# homeboard1.net
KiCad netlist of a schematic drawn in EAGLE
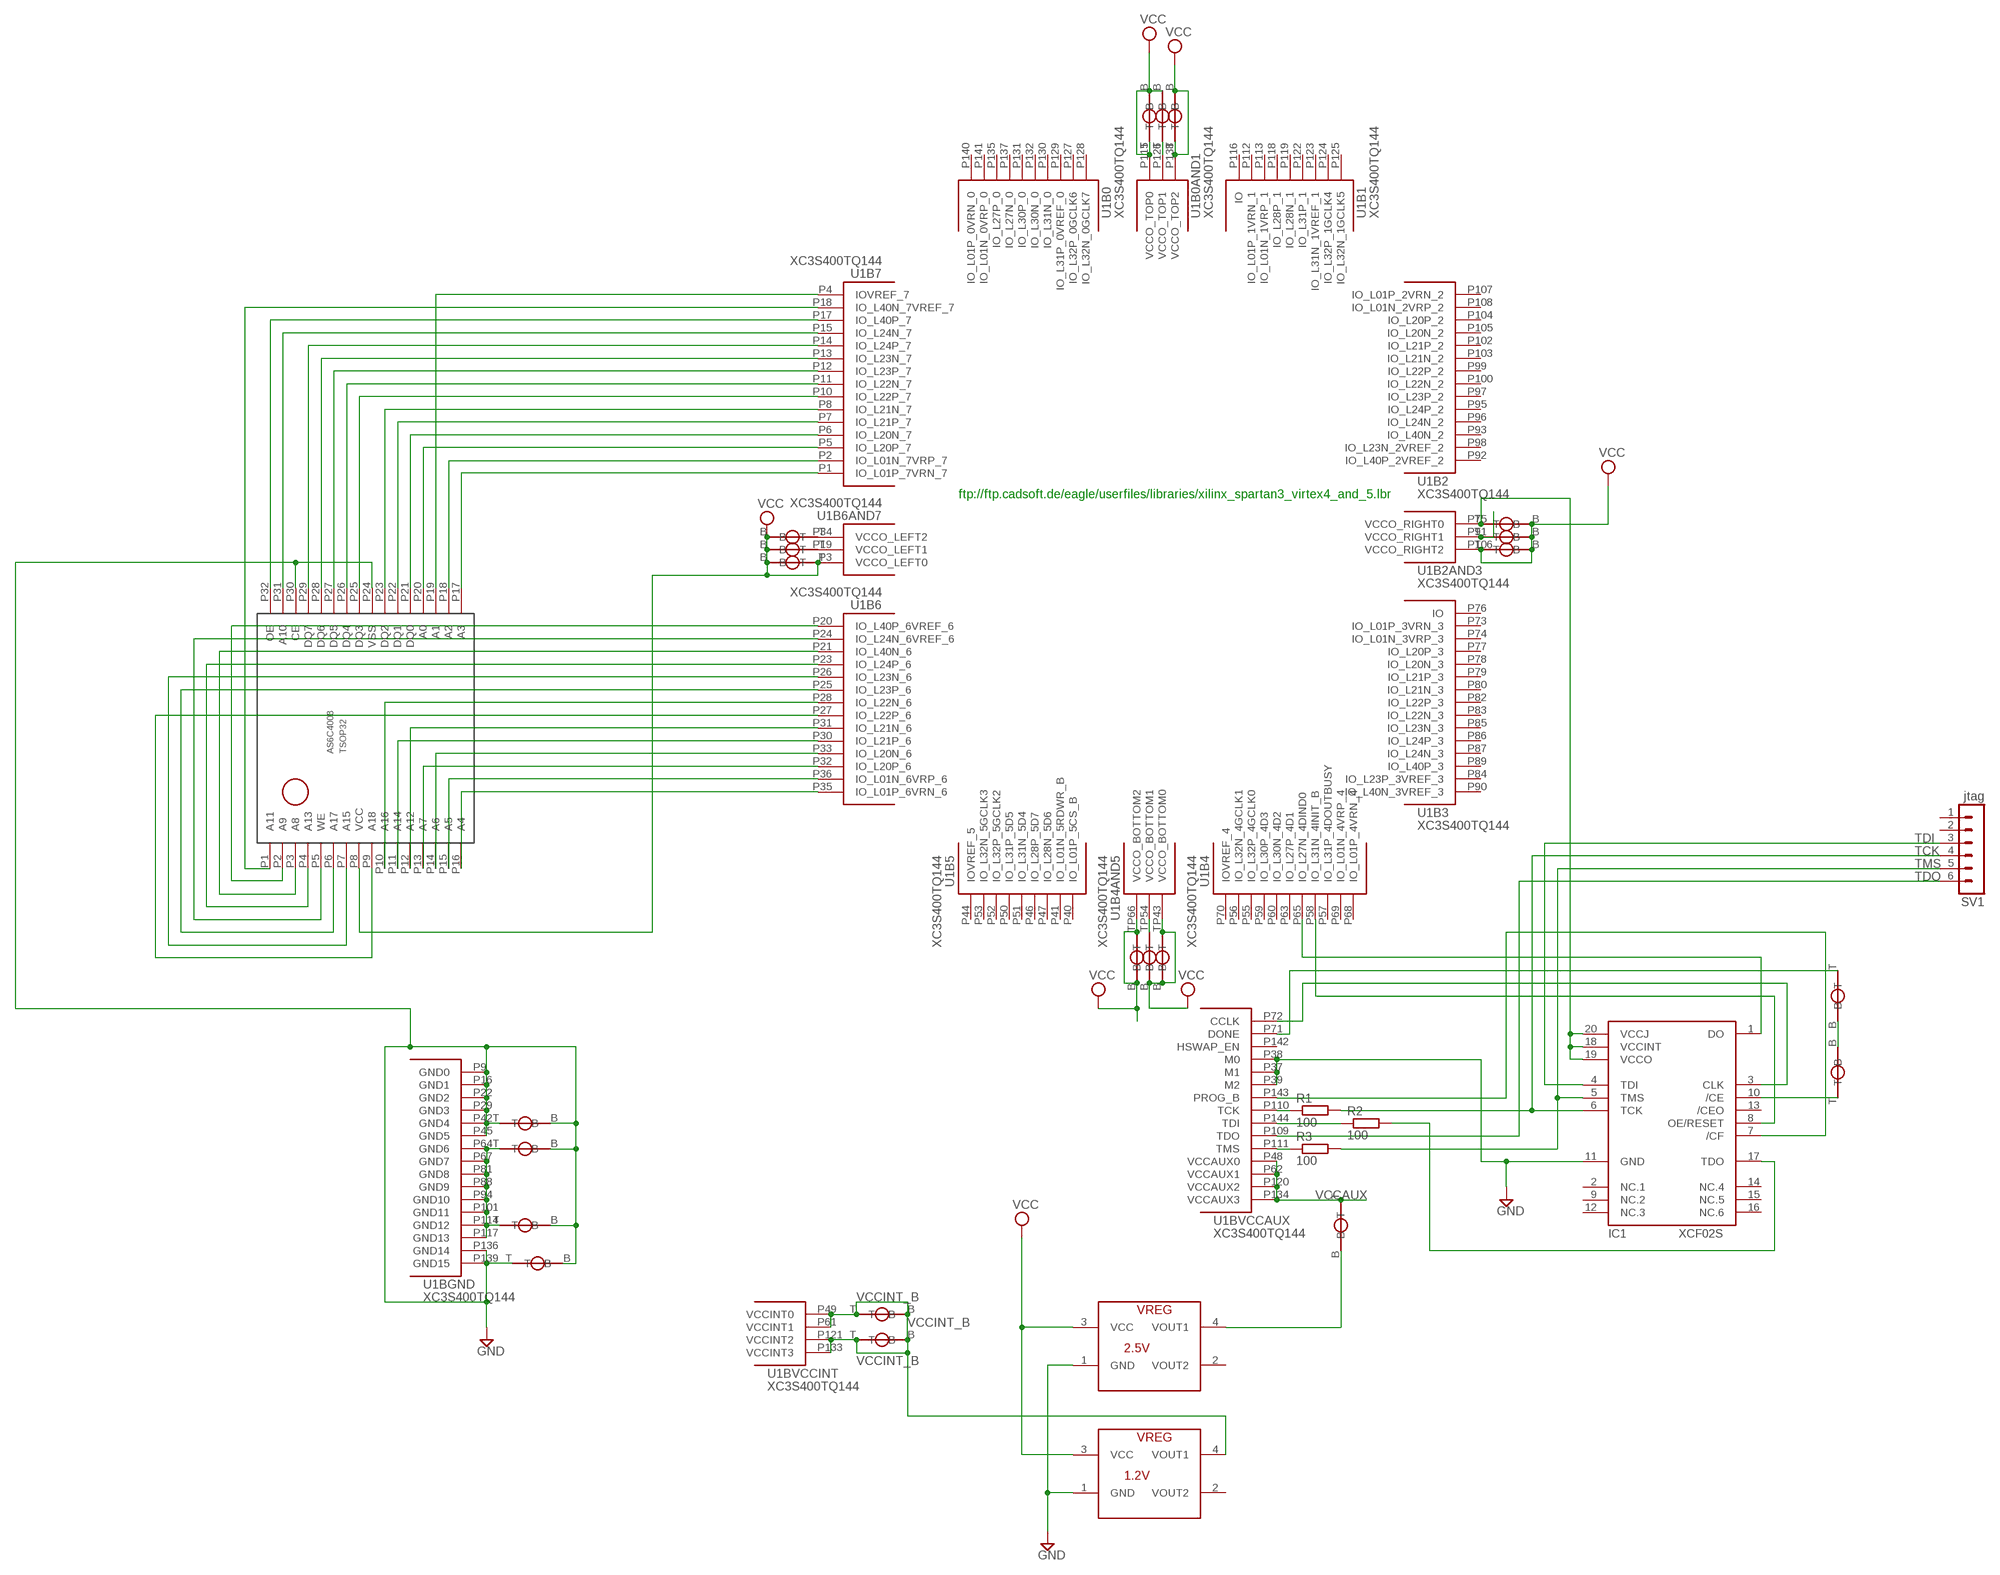
[diagram p0: schematic, sheet 1]

(export (version "E")
  (design (tool "Eeschema 10.0.6"))
  (components
    (comp (ref "IC1")
      (value "XCF02S")
      (footprint "eagle-import:VO20")
      (libsource (lib "eagle-import") (part "XCF02S"))
    )
    (comp (ref "R1")
      (value "100")
      (footprint "eagle-import:R0805")
      (libsource (lib "eagle-import") (part "R-EU_R0805"))
    )
    (comp (ref "R2")
      (value "100")
      (footprint "eagle-import:R0805")
      (libsource (lib "eagle-import") (part "R-EU_R0805"))
    )
    (comp (ref "R3")
      (value "100")
      (footprint "eagle-import:R0805")
      (libsource (lib "eagle-import") (part "R-EU_R0805"))
    )
    (comp (ref "SV1")
      (value "jtag")
      (footprint "eagle-import:MA06-1")
      (libsource (lib "eagle-import") (part "MA06-1"))
    )
    (comp (ref "U$1")
      (value "VIA_DIY")
      (footprint "eagle-import:VIA_DIY")
      (libsource (lib "eagle-import") (part "VIA_DIY"))
    )
    (comp (ref "U$2")
      (value "VIA_DIY")
      (footprint "eagle-import:VIA_DIY")
      (libsource (lib "eagle-import") (part "VIA_DIY"))
    )
    (comp (ref "U$3")
      (value "VIA_DIY")
      (footprint "eagle-import:VIA_DIY")
      (libsource (lib "eagle-import") (part "VIA_DIY"))
    )
    (comp (ref "U$4")
      (value "AS6C4008")
      (footprint "eagle-import:TSOP32")
      (libsource (lib "eagle-import") (part "AS6C4008"))
    )
    (comp (ref "U$5")
      (value "VIA_DIY")
      (footprint "eagle-import:VIA_DIY")
      (libsource (lib "eagle-import") (part "VIA_DIY"))
    )
    (comp (ref "U$6")
      (value "VIA_DIY")
      (footprint "eagle-import:VIA_DIY")
      (libsource (lib "eagle-import") (part "VIA_DIY"))
    )
    (comp (ref "U$7")
      (value "VIA_DIY")
      (footprint "eagle-import:VIA_DIY")
      (libsource (lib "eagle-import") (part "VIA_DIY"))
    )
    (comp (ref "U$8")
      (value "2.5V")
      (footprint "eagle-import:SOT223")
      (libsource (lib "eagle-import") (part "NX1117"))
    )
    (comp (ref "U$9")
      (value "1.2V")
      (footprint "eagle-import:SOT223")
      (libsource (lib "eagle-import") (part "NX1117"))
    )
    (comp (ref "U$10")
      (value "VIA_DIY")
      (footprint "eagle-import:VIA_DIY")
      (libsource (lib "eagle-import") (part "VIA_DIY"))
    )
    (comp (ref "U$11")
      (value "VIA_DIY")
      (footprint "eagle-import:VIA_DIY")
      (libsource (lib "eagle-import") (part "VIA_DIY"))
    )
    (comp (ref "U$12")
      (value "VIA_DIY")
      (footprint "eagle-import:VIA_DIY")
      (libsource (lib "eagle-import") (part "VIA_DIY"))
    )
    (comp (ref "U$13")
      (value "VIA_DIY")
      (footprint "eagle-import:VIA_DIY")
      (libsource (lib "eagle-import") (part "VIA_DIY"))
    )
    (comp (ref "U$14")
      (value "VIA_DIY")
      (footprint "eagle-import:VIA_DIY")
      (libsource (lib "eagle-import") (part "VIA_DIY"))
    )
    (comp (ref "U$15")
      (value "VIA_DIY")
      (footprint "eagle-import:VIA_DIY")
      (libsource (lib "eagle-import") (part "VIA_DIY"))
    )
    (comp (ref "U$18")
      (value "VIA_DIY")
      (footprint "eagle-import:VIA_DIY")
      (libsource (lib "eagle-import") (part "VIA_DIY"))
    )
    (comp (ref "U$19")
      (value "VIA_DIY")
      (footprint "eagle-import:VIA_DIY")
      (libsource (lib "eagle-import") (part "VIA_DIY"))
    )
    (comp (ref "U$20")
      (value "VIA_DIY")
      (footprint "eagle-import:VIA_DIY")
      (libsource (lib "eagle-import") (part "VIA_DIY"))
    )
    (comp (ref "U$23")
      (value "VIA_DIY")
      (footprint "eagle-import:VIA_DIY")
      (libsource (lib "eagle-import") (part "VIA_DIY"))
    )
    (comp (ref "U$25")
      (value "VIA_DIY")
      (footprint "eagle-import:VIA_DIY")
      (libsource (lib "eagle-import") (part "VIA_DIY"))
    )
    (comp (ref "U$26")
      (value "VIA_DIY")
      (footprint "eagle-import:VIA_DIY")
      (libsource (lib "eagle-import") (part "VIA_DIY"))
    )
    (comp (ref "U$27")
      (value "VIA_DIY")
      (footprint "eagle-import:VIA_DIY")
      (libsource (lib "eagle-import") (part "VIA_DIY"))
    )
    (comp (ref "U$28")
      (value "VIA_DIY")
      (footprint "eagle-import:VIA_DIY")
      (libsource (lib "eagle-import") (part "VIA_DIY"))
    )
    (comp (ref "U$29")
      (value "VIA_DIY")
      (footprint "eagle-import:VIA_DIY")
      (libsource (lib "eagle-import") (part "VIA_DIY"))
    )
    (comp (ref "U1")
      (value "XC3S400TQ144")
      (footprint "eagle-import:TQ144")
      (libsource (lib "eagle-import") (part "XC3S400TQ144"))
    )
  )
  (nets
    (net (code "1") (name "/TCK") (class "Default")
      (node (ref "IC1") (pin "6") (pinfunction "TCK_6") (pintype "bidirectional"))
      (node (ref "R1") (pin "2") (pinfunction "2_2") (pintype "passive"))
      (node (ref "SV1") (pin "4") (pinfunction "4_4") (pintype "passive"))
    )
    (net (code "2") (name "/TDI") (class "Default")
      (node (ref "IC1") (pin "4") (pinfunction "TDI_4") (pintype "bidirectional"))
      (node (ref "SV1") (pin "3") (pinfunction "3_3") (pintype "passive"))
    )
    (net (code "3") (name "/TDO") (class "Default")
      (node (ref "SV1") (pin "6") (pinfunction "6_6") (pintype "passive"))
      (node (ref "U1") (pin "P109") (pinfunction "TDO_P109") (pintype "bidirectional"))
    )
    (net (code "4") (name "/TMS") (class "Default")
      (node (ref "IC1") (pin "5") (pinfunction "TMS_5") (pintype "bidirectional"))
      (node (ref "R3") (pin "2") (pinfunction "2_2") (pintype "passive"))
      (node (ref "SV1") (pin "5") (pinfunction "5_5") (pintype "passive"))
    )
    (net (code "5") (name "/VCCAUX") (class "Default")
      (node (ref "U$11") (pin "T") (pinfunction "T_T") (pintype "bidirectional"))
      (node (ref "U1") (pin "P120") (pinfunction "VCCAUX2_P120") (pintype "passive"))
      (node (ref "U1") (pin "P134") (pinfunction "VCCAUX3_P134") (pintype "passive"))
      (node (ref "U1") (pin "P48") (pinfunction "VCCAUX0_P48") (pintype "passive"))
      (node (ref "U1") (pin "P62") (pinfunction "VCCAUX1_P62") (pintype "passive"))
    )
    (net (code "6") (name "/VCCINT_B") (class "Default")
      (node (ref "U$1") (pin "B") (pinfunction "B_B") (pintype "bidirectional"))
      (node (ref "U$1") (pin "T") (pinfunction "T_T") (pintype "bidirectional"))
      (node (ref "U$23") (pin "B") (pinfunction "B_B") (pintype "bidirectional"))
      (node (ref "U$23") (pin "T") (pinfunction "T_T") (pintype "bidirectional"))
      (node (ref "U$9") (pin "4") (pinfunction "VOUT1_4") (pintype "bidirectional"))
      (node (ref "U1") (pin "P121") (pinfunction "VCCINT2_P121") (pintype "passive"))
      (node (ref "U1") (pin "P133") (pinfunction "VCCINT3_P133") (pintype "passive"))
      (node (ref "U1") (pin "P49") (pinfunction "VCCINT0_P49") (pintype "passive"))
      (node (ref "U1") (pin "P61") (pinfunction "VCCINT1_P61") (pintype "passive"))
    )
    (net (code "7") (name "GND") (class "Default")
      (node (ref "IC1") (pin "11") (pinfunction "GND_11") (pintype "bidirectional"))
      (node (ref "U$2") (pin "B") (pinfunction "B_B") (pintype "bidirectional"))
      (node (ref "U$20") (pin "B") (pinfunction "B_B") (pintype "bidirectional"))
      (node (ref "U$3") (pin "B") (pinfunction "B_B") (pintype "bidirectional"))
      (node (ref "U$3") (pin "T") (pinfunction "T_T") (pintype "bidirectional"))
      (node (ref "U$4") (pin "P24") (pinfunction "VSS_P24") (pintype "bidirectional"))
      (node (ref "U$4") (pin "P30") (pinfunction "CE_P30") (pintype "bidirectional"))
      (node (ref "U$5") (pin "B") (pinfunction "B_B") (pintype "bidirectional"))
      (node (ref "U$5") (pin "T") (pinfunction "T_T") (pintype "bidirectional"))
      (node (ref "U$8") (pin "1") (pinfunction "GND_1") (pintype "bidirectional"))
      (node (ref "U$9") (pin "1") (pinfunction "GND_1") (pintype "bidirectional"))
      (node (ref "U1") (pin "P136") (pinfunction "GND14_P136") (pintype "passive"))
      (node (ref "U1") (pin "P139") (pinfunction "GND15_P139") (pintype "passive"))
      (node (ref "U1") (pin "P16") (pinfunction "GND1_P16") (pintype "passive"))
      (node (ref "U1") (pin "P22") (pinfunction "GND2_P22") (pintype "passive"))
      (node (ref "U1") (pin "P29") (pinfunction "GND3_P29") (pintype "passive"))
      (node (ref "U1") (pin "P37") (pinfunction "M1_P37") (pintype "bidirectional"))
      (node (ref "U1") (pin "P38") (pinfunction "M0_P38") (pintype "bidirectional"))
      (node (ref "U1") (pin "P39") (pinfunction "M2_P39") (pintype "bidirectional"))
      (node (ref "U1") (pin "P42") (pinfunction "GND4_P42") (pintype "passive"))
      (node (ref "U1") (pin "P45") (pinfunction "GND5_P45") (pintype "passive"))
      (node (ref "U1") (pin "P9") (pinfunction "GND0_P9") (pintype "passive"))
    )
    (net (code "8") (name "Net-(IC1-CLK)") (class "Default")
      (node (ref "IC1") (pin "3") (pinfunction "CLK_3") (pintype "bidirectional"))
      (node (ref "U1") (pin "P72") (pinfunction "CCLK_P72") (pintype "bidirectional"))
    )
    (net (code "9") (name "Net-(IC1-DO)") (class "Default")
      (node (ref "IC1") (pin "1") (pinfunction "DO_1") (pintype "bidirectional"))
      (node (ref "U1") (pin "P65") (pinfunction "IO_L27N_4DIND0_P65") (pintype "bidirectional"))
    )
    (net (code "10") (name "Net-(IC1-OE{slash}RESET)") (class "Default")
      (node (ref "IC1") (pin "8") (pinfunction "OE/RESET_8") (pintype "bidirectional"))
      (node (ref "U1") (pin "P58") (pinfunction "IO_L31N_4INIT_B_P58") (pintype "bidirectional"))
    )
    (net (code "11") (name "Net-(IC1-TDO)") (class "Default")
      (node (ref "IC1") (pin "17") (pinfunction "TDO_17") (pintype "bidirectional"))
      (node (ref "R2") (pin "2") (pinfunction "2_2") (pintype "passive"))
    )
    (net (code "12") (name "Net-(IC1-VCCINT)") (class "Default")
      (node (ref "IC1") (pin "18") (pinfunction "VCCINT_18") (pintype "bidirectional"))
      (node (ref "IC1") (pin "19") (pinfunction "VCCO_19") (pintype "bidirectional"))
      (node (ref "IC1") (pin "20") (pinfunction "VCCJ_20") (pintype "bidirectional"))
      (node (ref "U$29") (pin "T") (pinfunction "T_T") (pintype "bidirectional"))
      (node (ref "U1") (pin "P75") (pinfunction "VCCO_RIGHT0_P75") (pintype "passive"))
    )
    (net (code "13") (name "Net-(IC1-{slash}CE)") (class "Default")
      (node (ref "IC1") (pin "10") (pinfunction "/CE_10") (pintype "bidirectional"))
      (node (ref "U$12") (pin "T") (pinfunction "T_T") (pintype "bidirectional"))
    )
    (net (code "14") (name "Net-(IC1-{slash}CF)") (class "Default")
      (node (ref "IC1") (pin "7") (pinfunction "/CF_7") (pintype "bidirectional"))
      (node (ref "U1") (pin "P143") (pinfunction "PROG_B_P143") (pintype "bidirectional"))
    )
    (net (code "15") (name "Net-(U$4-A0)") (class "Default")
      (node (ref "U$4") (pin "P20") (pinfunction "A0_P20") (pintype "bidirectional"))
      (node (ref "U1") (pin "P5") (pinfunction "IO_L20P_7_P5") (pintype "bidirectional"))
    )
    (net (code "16") (name "Net-(U$4-A1)") (class "Default")
      (node (ref "U$4") (pin "P19") (pinfunction "A1_P19") (pintype "bidirectional"))
      (node (ref "U1") (pin "P4") (pinfunction "IOVREF_7_P4") (pintype "bidirectional"))
    )
    (net (code "17") (name "Net-(U$4-A2)") (class "Default")
      (node (ref "U$4") (pin "P18") (pinfunction "A2_P18") (pintype "bidirectional"))
      (node (ref "U1") (pin "P2") (pinfunction "IO_L01N_7VRP_7_P2") (pintype "bidirectional"))
    )
    (net (code "18") (name "Net-(U$4-A3)") (class "Default")
      (node (ref "U$4") (pin "P17") (pinfunction "A3_P17") (pintype "bidirectional"))
      (node (ref "U1") (pin "P1") (pinfunction "IO_L01P_7VRN_7_P1") (pintype "bidirectional"))
    )
    (net (code "19") (name "Net-(U$4-A4)") (class "Default")
      (node (ref "U$4") (pin "P16") (pinfunction "A4_P16") (pintype "bidirectional"))
      (node (ref "U1") (pin "P35") (pinfunction "IO_L01P_6VRN_6_P35") (pintype "bidirectional"))
    )
    (net (code "20") (name "Net-(U$4-A5)") (class "Default")
      (node (ref "U$4") (pin "P15") (pinfunction "A5_P15") (pintype "bidirectional"))
      (node (ref "U1") (pin "P36") (pinfunction "IO_L01N_6VRP_6_P36") (pintype "bidirectional"))
    )
    (net (code "21") (name "Net-(U$4-A6)") (class "Default")
      (node (ref "U$4") (pin "P14") (pinfunction "A6_P14") (pintype "bidirectional"))
      (node (ref "U1") (pin "P33") (pinfunction "IO_L20N_6_P33") (pintype "bidirectional"))
    )
    (net (code "22") (name "Net-(U$4-A7)") (class "Default")
      (node (ref "U$4") (pin "P13") (pinfunction "A7_P13") (pintype "bidirectional"))
      (node (ref "U1") (pin "P32") (pinfunction "IO_L20P_6_P32") (pintype "bidirectional"))
    )
    (net (code "23") (name "Net-(U$4-A8)") (class "Default")
      (node (ref "U$4") (pin "P3") (pinfunction "A8_P3") (pintype "bidirectional"))
      (node (ref "U1") (pin "P21") (pinfunction "IO_L40N_6_P21") (pintype "bidirectional"))
    )
    (net (code "24") (name "Net-(U$4-A9)") (class "Default")
      (node (ref "U$4") (pin "P2") (pinfunction "A9_P2") (pintype "bidirectional"))
      (node (ref "U1") (pin "P20") (pinfunction "IO_L40P_6VREF_6_P20") (pintype "bidirectional"))
    )
    (net (code "25") (name "Net-(U$4-A10)") (class "Default")
      (node (ref "U$4") (pin "P31") (pinfunction "A10_P31") (pintype "bidirectional"))
      (node (ref "U1") (pin "P15") (pinfunction "IO_L24N_7_P15") (pintype "bidirectional"))
    )
    (net (code "26") (name "Net-(U$4-A11)") (class "Default")
      (node (ref "U$4") (pin "P1") (pinfunction "A11_P1") (pintype "bidirectional"))
      (node (ref "U1") (pin "P18") (pinfunction "IO_L40N_7VREF_7_P18") (pintype "bidirectional"))
    )
    (net (code "27") (name "Net-(U$4-A12)") (class "Default")
      (node (ref "U$4") (pin "P12") (pinfunction "A12_P12") (pintype "bidirectional"))
      (node (ref "U1") (pin "P31") (pinfunction "IO_L21N_6_P31") (pintype "bidirectional"))
    )
    (net (code "28") (name "Net-(U$4-A13)") (class "Default")
      (node (ref "U$4") (pin "P4") (pinfunction "A13_P4") (pintype "bidirectional"))
      (node (ref "U1") (pin "P23") (pinfunction "IO_L24P_6_P23") (pintype "bidirectional"))
    )
    (net (code "29") (name "Net-(U$4-A14)") (class "Default")
      (node (ref "U$4") (pin "P11") (pinfunction "A14_P11") (pintype "bidirectional"))
      (node (ref "U1") (pin "P30") (pinfunction "IO_L21P_6_P30") (pintype "bidirectional"))
    )
    (net (code "30") (name "Net-(U$4-A15)") (class "Default")
      (node (ref "U$4") (pin "P7") (pinfunction "A15_P7") (pintype "bidirectional"))
      (node (ref "U1") (pin "P26") (pinfunction "IO_L23N_6_P26") (pintype "bidirectional"))
    )
    (net (code "31") (name "Net-(U$4-A16)") (class "Default")
      (node (ref "U$4") (pin "P10") (pinfunction "A16_P10") (pintype "bidirectional"))
      (node (ref "U1") (pin "P28") (pinfunction "IO_L22N_6_P28") (pintype "bidirectional"))
    )
    (net (code "32") (name "Net-(U$4-A17)") (class "Default")
      (node (ref "U$4") (pin "P6") (pinfunction "A17_P6") (pintype "bidirectional"))
      (node (ref "U1") (pin "P25") (pinfunction "IO_L23P_6_P25") (pintype "bidirectional"))
    )
    (net (code "33") (name "Net-(U$4-A18)") (class "Default")
      (node (ref "U$4") (pin "P9") (pinfunction "A18_P9") (pintype "bidirectional"))
      (node (ref "U1") (pin "P27") (pinfunction "IO_L22P_6_P27") (pintype "bidirectional"))
    )
    (net (code "34") (name "Net-(U$4-DQ0)") (class "Default")
      (node (ref "U$4") (pin "P21") (pinfunction "DQ0_P21") (pintype "bidirectional"))
      (node (ref "U1") (pin "P6") (pinfunction "IO_L20N_7_P6") (pintype "bidirectional"))
    )
    (net (code "35") (name "Net-(U$4-DQ1)") (class "Default")
      (node (ref "U$4") (pin "P22") (pinfunction "DQ1_P22") (pintype "bidirectional"))
      (node (ref "U1") (pin "P7") (pinfunction "IO_L21P_7_P7") (pintype "bidirectional"))
    )
    (net (code "36") (name "Net-(U$4-DQ2)") (class "Default")
      (node (ref "U$4") (pin "P23") (pinfunction "DQ2_P23") (pintype "bidirectional"))
      (node (ref "U1") (pin "P8") (pinfunction "IO_L21N_7_P8") (pintype "bidirectional"))
    )
    (net (code "37") (name "Net-(U$4-DQ3)") (class "Default")
      (node (ref "U$4") (pin "P25") (pinfunction "DQ3_P25") (pintype "bidirectional"))
      (node (ref "U1") (pin "P10") (pinfunction "IO_L22P_7_P10") (pintype "bidirectional"))
    )
    (net (code "38") (name "Net-(U$4-DQ4)") (class "Default")
      (node (ref "U$4") (pin "P26") (pinfunction "DQ4_P26") (pintype "bidirectional"))
      (node (ref "U1") (pin "P11") (pinfunction "IO_L22N_7_P11") (pintype "bidirectional"))
    )
    (net (code "39") (name "Net-(U$4-DQ5)") (class "Default")
      (node (ref "U$4") (pin "P27") (pinfunction "DQ5_P27") (pintype "bidirectional"))
      (node (ref "U1") (pin "P12") (pinfunction "IO_L23P_7_P12") (pintype "bidirectional"))
    )
    (net (code "40") (name "Net-(U$4-DQ6)") (class "Default")
      (node (ref "U$4") (pin "P28") (pinfunction "DQ6_P28") (pintype "bidirectional"))
      (node (ref "U1") (pin "P13") (pinfunction "IO_L23N_7_P13") (pintype "bidirectional"))
    )
    (net (code "41") (name "Net-(U$4-DQ7)") (class "Default")
      (node (ref "U$4") (pin "P29") (pinfunction "DQ7_P29") (pintype "bidirectional"))
      (node (ref "U1") (pin "P14") (pinfunction "IO_L24P_7_P14") (pintype "bidirectional"))
    )
    (net (code "42") (name "Net-(U$4-OE)") (class "Default")
      (node (ref "U$4") (pin "P32") (pinfunction "OE_P32") (pintype "bidirectional"))
      (node (ref "U1") (pin "P17") (pinfunction "IO_L40P_7_P17") (pintype "bidirectional"))
    )
    (net (code "43") (name "Net-(U$4-WE)") (class "Default")
      (node (ref "U$4") (pin "P5") (pinfunction "WE_P5") (pintype "bidirectional"))
      (node (ref "U1") (pin "P24") (pinfunction "IO_L24N_6VREF_6_P24") (pintype "bidirectional"))
    )
    (net (code "44") (name "Net-(U$8-VOUT1)") (class "Default")
      (node (ref "U$11") (pin "B") (pinfunction "B_B") (pintype "bidirectional"))
      (node (ref "U$8") (pin "4") (pinfunction "VOUT1_4") (pintype "bidirectional"))
    )
    (net (code "45") (name "Net-(U$12-PadB)") (class "Default")
      (node (ref "U$12") (pin "B") (pinfunction "B_B") (pintype "bidirectional"))
      (node (ref "U$13") (pin "B") (pinfunction "B_B") (pintype "bidirectional"))
    )
    (net (code "46") (name "Net-(U1B-VCCO_TOP1)") (class "Default")
      (node (ref "U$10") (pin "T") (pinfunction "T_T") (pintype "bidirectional"))
      (node (ref "U1") (pin "P126") (pinfunction "VCCO_TOP1_P126") (pintype "passive"))
    )
    (net (code "47") (name "Net-(U1E-VCCO_RIGHT1)") (class "Default")
      (node (ref "U$28") (pin "T") (pinfunction "T_T") (pintype "bidirectional"))
      (node (ref "U1") (pin "P91") (pinfunction "VCCO_RIGHT1_P91") (pintype "passive"))
    )
    (net (code "48") (name "Net-(U1H-VCCO_BOTTOM1)") (class "Default")
      (node (ref "U$25") (pin "T") (pinfunction "T_T") (pintype "bidirectional"))
      (node (ref "U1") (pin "P54") (pinfunction "VCCO_BOTTOM1_P54") (pintype "passive"))
    )
    (net (code "49") (name "Net-(U1K-VCCO_LEFT1)") (class "Default")
      (node (ref "U$15") (pin "T") (pinfunction "T_T") (pintype "bidirectional"))
      (node (ref "U1") (pin "P19") (pinfunction "VCCO_LEFT1_P19") (pintype "passive"))
    )
    (net (code "50") (name "Net-(U1K-VCCO_LEFT2)") (class "Default")
      (node (ref "U$14") (pin "T") (pinfunction "T_T") (pintype "bidirectional"))
      (node (ref "U1") (pin "P34") (pinfunction "VCCO_LEFT2_P34") (pintype "passive"))
    )
    (net (code "51") (name "Net-(U1M-GND10)") (class "Default")
      (node (ref "U$2") (pin "T") (pinfunction "T_T") (pintype "bidirectional"))
      (node (ref "U$20") (pin "T") (pinfunction "T_T") (pintype "bidirectional"))
      (node (ref "U1") (pin "P101") (pinfunction "GND11_P101") (pintype "passive"))
      (node (ref "U1") (pin "P114") (pinfunction "GND12_P114") (pintype "passive"))
      (node (ref "U1") (pin "P117") (pinfunction "GND13_P117") (pintype "passive"))
      (node (ref "U1") (pin "P64") (pinfunction "GND6_P64") (pintype "passive"))
      (node (ref "U1") (pin "P67") (pinfunction "GND7_P67") (pintype "passive"))
      (node (ref "U1") (pin "P81") (pinfunction "GND8_P81") (pintype "passive"))
      (node (ref "U1") (pin "P88") (pinfunction "GND9_P88") (pintype "passive"))
      (node (ref "U1") (pin "P94") (pinfunction "GND10_P94") (pintype "passive"))
    )
    (net (code "52") (name "Net-(U1N-DONE)") (class "Default")
      (node (ref "U$13") (pin "T") (pinfunction "T_T") (pintype "bidirectional"))
      (node (ref "U1") (pin "P71") (pinfunction "DONE_P71") (pintype "bidirectional"))
    )
    (net (code "53") (name "Net-(U1N-TCK)") (class "Default")
      (node (ref "R1") (pin "1") (pinfunction "1_1") (pintype "passive"))
      (node (ref "U1") (pin "P110") (pinfunction "TCK_P110") (pintype "bidirectional"))
    )
    (net (code "54") (name "Net-(U1N-TDI)") (class "Default")
      (node (ref "R2") (pin "1") (pinfunction "1_1") (pintype "passive"))
      (node (ref "U1") (pin "P144") (pinfunction "TDI_P144") (pintype "bidirectional"))
    )
    (net (code "55") (name "Net-(U1N-TMS)") (class "Default")
      (node (ref "R3") (pin "1") (pinfunction "1_1") (pintype "passive"))
      (node (ref "U1") (pin "P111") (pinfunction "TMS_P111") (pintype "bidirectional"))
    )
    (net (code "56") (name "VCC") (class "Default")
      (node (ref "U$10") (pin "B") (pinfunction "B_B") (pintype "bidirectional"))
      (node (ref "U$14") (pin "B") (pinfunction "B_B") (pintype "bidirectional"))
      (node (ref "U$15") (pin "B") (pinfunction "B_B") (pintype "bidirectional"))
      (node (ref "U$18") (pin "B") (pinfunction "B_B") (pintype "bidirectional"))
      (node (ref "U$18") (pin "T") (pinfunction "T_T") (pintype "bidirectional"))
      (node (ref "U$19") (pin "B") (pinfunction "B_B") (pintype "bidirectional"))
      (node (ref "U$19") (pin "T") (pinfunction "T_T") (pintype "bidirectional"))
      (node (ref "U$25") (pin "B") (pinfunction "B_B") (pintype "bidirectional"))
      (node (ref "U$26") (pin "B") (pinfunction "B_B") (pintype "bidirectional"))
      (node (ref "U$26") (pin "T") (pinfunction "T_T") (pintype "bidirectional"))
      (node (ref "U$27") (pin "B") (pinfunction "B_B") (pintype "bidirectional"))
      (node (ref "U$27") (pin "T") (pinfunction "T_T") (pintype "bidirectional"))
      (node (ref "U$28") (pin "B") (pinfunction "B_B") (pintype "bidirectional"))
      (node (ref "U$29") (pin "B") (pinfunction "B_B") (pintype "bidirectional"))
      (node (ref "U$4") (pin "P8") (pinfunction "VCC_P8") (pintype "bidirectional"))
      (node (ref "U$6") (pin "B") (pinfunction "B_B") (pintype "bidirectional"))
      (node (ref "U$6") (pin "T") (pinfunction "T_T") (pintype "bidirectional"))
      (node (ref "U$7") (pin "B") (pinfunction "B_B") (pintype "bidirectional"))
      (node (ref "U$7") (pin "T") (pinfunction "T_T") (pintype "bidirectional"))
      (node (ref "U$8") (pin "3") (pinfunction "VCC_3") (pintype "bidirectional"))
      (node (ref "U$9") (pin "3") (pinfunction "VCC_3") (pintype "bidirectional"))
      (node (ref "U1") (pin "P106") (pinfunction "VCCO_RIGHT2_P106") (pintype "passive"))
      (node (ref "U1") (pin "P115") (pinfunction "VCCO_TOP0_P115") (pintype "passive"))
      (node (ref "U1") (pin "P138") (pinfunction "VCCO_TOP2_P138") (pintype "passive"))
      (node (ref "U1") (pin "P3") (pinfunction "VCCO_LEFT0_P3") (pintype "passive"))
      (node (ref "U1") (pin "P43") (pinfunction "VCCO_BOTTOM0_P43") (pintype "passive"))
      (node (ref "U1") (pin "P66") (pinfunction "VCCO_BOTTOM2_P66") (pintype "passive"))
    )
    (net (code "57") (name "unconnected-(IC1-NC.1-Pad2)") (class "Default")
      (node (ref "IC1") (pin "2") (pinfunction "NC.1_2") (pintype "bidirectional"))
    )
    (net (code "58") (name "unconnected-(IC1-NC.2-Pad9)") (class "Default")
      (node (ref "IC1") (pin "9") (pinfunction "NC.2_9") (pintype "bidirectional"))
    )
    (net (code "59") (name "unconnected-(IC1-NC.3-Pad12)") (class "Default")
      (node (ref "IC1") (pin "12") (pinfunction "NC.3_12") (pintype "bidirectional"))
    )
    (net (code "60") (name "unconnected-(IC1-NC.4-Pad14)") (class "Default")
      (node (ref "IC1") (pin "14") (pinfunction "NC.4_14") (pintype "bidirectional"))
    )
    (net (code "61") (name "unconnected-(IC1-NC.5-Pad15)") (class "Default")
      (node (ref "IC1") (pin "15") (pinfunction "NC.5_15") (pintype "bidirectional"))
    )
    (net (code "62") (name "unconnected-(IC1-NC.6-Pad16)") (class "Default")
      (node (ref "IC1") (pin "16") (pinfunction "NC.6_16") (pintype "bidirectional"))
    )
    (net (code "63") (name "unconnected-(IC1-{slash}CEO-Pad13)") (class "Default")
      (node (ref "IC1") (pin "13") (pinfunction "/CEO_13") (pintype "bidirectional"))
    )
    (net (code "64") (name "unconnected-(SV1-Pad1)") (class "Default")
      (node (ref "SV1") (pin "1") (pinfunction "1_1") (pintype "passive"))
    )
    (net (code "65") (name "unconnected-(SV1-Pad2)") (class "Default")
      (node (ref "SV1") (pin "2") (pinfunction "2_2") (pintype "passive"))
    )
    (net (code "66") (name "unconnected-(U$8-VOUT2-Pad2)") (class "Default")
      (node (ref "U$8") (pin "2") (pinfunction "VOUT2_2") (pintype "bidirectional"))
    )
    (net (code "67") (name "unconnected-(U$9-VOUT2-Pad2)") (class "Default")
      (node (ref "U$9") (pin "2") (pinfunction "VOUT2_2") (pintype "bidirectional"))
    )
    (net (code "68") (name "unconnected-(U1A-IO_L01N_0VRP_0-PadP141)") (class "Default")
      (node (ref "U1") (pin "P141") (pinfunction "IO_L01N_0VRP_0_P141") (pintype "bidirectional"))
    )
    (net (code "69") (name "unconnected-(U1A-IO_L01P_0VRN_0-PadP140)") (class "Default")
      (node (ref "U1") (pin "P140") (pinfunction "IO_L01P_0VRN_0_P140") (pintype "bidirectional"))
    )
    (net (code "70") (name "unconnected-(U1A-IO_L27N_0-PadP137)") (class "Default")
      (node (ref "U1") (pin "P137") (pinfunction "IO_L27N_0_P137") (pintype "bidirectional"))
    )
    (net (code "71") (name "unconnected-(U1A-IO_L27P_0-PadP135)") (class "Default")
      (node (ref "U1") (pin "P135") (pinfunction "IO_L27P_0_P135") (pintype "bidirectional"))
    )
    (net (code "72") (name "unconnected-(U1A-IO_L30N_0-PadP132)") (class "Default")
      (node (ref "U1") (pin "P132") (pinfunction "IO_L30N_0_P132") (pintype "bidirectional"))
    )
    (net (code "73") (name "unconnected-(U1A-IO_L30P_0-PadP131)") (class "Default")
      (node (ref "U1") (pin "P131") (pinfunction "IO_L30P_0_P131") (pintype "bidirectional"))
    )
    (net (code "74") (name "unconnected-(U1A-IO_L31N_0-PadP130)") (class "Default")
      (node (ref "U1") (pin "P130") (pinfunction "IO_L31N_0_P130") (pintype "bidirectional"))
    )
    (net (code "75") (name "unconnected-(U1A-IO_L31P_0VREF_0-PadP129)") (class "Default")
      (node (ref "U1") (pin "P129") (pinfunction "IO_L31P_0VREF_0_P129") (pintype "bidirectional"))
    )
    (net (code "76") (name "unconnected-(U1A-IO_L32N_0GCLK7-PadP128)") (class "Default")
      (node (ref "U1") (pin "P128") (pinfunction "IO_L32N_0GCLK7_P128") (pintype "bidirectional"))
    )
    (net (code "77") (name "unconnected-(U1A-IO_L32P_0GCLK6-PadP127)") (class "Default")
      (node (ref "U1") (pin "P127") (pinfunction "IO_L32P_0GCLK6_P127") (pintype "bidirectional"))
    )
    (net (code "78") (name "unconnected-(U1C-IO-PadP116)") (class "Default")
      (node (ref "U1") (pin "P116") (pinfunction "IO_P116") (pintype "bidirectional"))
    )
    (net (code "79") (name "unconnected-(U1C-IO_L01N_1VRP_1-PadP113)") (class "Default")
      (node (ref "U1") (pin "P113") (pinfunction "IO_L01N_1VRP_1_P113") (pintype "bidirectional"))
    )
    (net (code "80") (name "unconnected-(U1C-IO_L01P_1VRN_1-PadP112)") (class "Default")
      (node (ref "U1") (pin "P112") (pinfunction "IO_L01P_1VRN_1_P112") (pintype "bidirectional"))
    )
    (net (code "81") (name "unconnected-(U1C-IO_L28N_1-PadP119)") (class "Default")
      (node (ref "U1") (pin "P119") (pinfunction "IO_L28N_1_P119") (pintype "bidirectional"))
    )
    (net (code "82") (name "unconnected-(U1C-IO_L28P_1-PadP118)") (class "Default")
      (node (ref "U1") (pin "P118") (pinfunction "IO_L28P_1_P118") (pintype "bidirectional"))
    )
    (net (code "83") (name "unconnected-(U1C-IO_L31N_1VREF_1-PadP123)") (class "Default")
      (node (ref "U1") (pin "P123") (pinfunction "IO_L31N_1VREF_1_P123") (pintype "bidirectional"))
    )
    (net (code "84") (name "unconnected-(U1C-IO_L31P_1-PadP122)") (class "Default")
      (node (ref "U1") (pin "P122") (pinfunction "IO_L31P_1_P122") (pintype "bidirectional"))
    )
    (net (code "85") (name "unconnected-(U1C-IO_L32N_1GCLK5-PadP125)") (class "Default")
      (node (ref "U1") (pin "P125") (pinfunction "IO_L32N_1GCLK5_P125") (pintype "bidirectional"))
    )
    (net (code "86") (name "unconnected-(U1C-IO_L32P_1GCLK4-PadP124)") (class "Default")
      (node (ref "U1") (pin "P124") (pinfunction "IO_L32P_1GCLK4_P124") (pintype "bidirectional"))
    )
    (net (code "87") (name "unconnected-(U1D-IO_L01N_2VRP_2-PadP108)") (class "Default")
      (node (ref "U1") (pin "P108") (pinfunction "IO_L01N_2VRP_2_P108") (pintype "bidirectional"))
    )
    (net (code "88") (name "unconnected-(U1D-IO_L01P_2VRN_2-PadP107)") (class "Default")
      (node (ref "U1") (pin "P107") (pinfunction "IO_L01P_2VRN_2_P107") (pintype "bidirectional"))
    )
    (net (code "89") (name "unconnected-(U1D-IO_L20N_2-PadP105)") (class "Default")
      (node (ref "U1") (pin "P105") (pinfunction "IO_L20N_2_P105") (pintype "bidirectional"))
    )
    (net (code "90") (name "unconnected-(U1D-IO_L20P_2-PadP104)") (class "Default")
      (node (ref "U1") (pin "P104") (pinfunction "IO_L20P_2_P104") (pintype "bidirectional"))
    )
    (net (code "91") (name "unconnected-(U1D-IO_L21N_2-PadP103)") (class "Default")
      (node (ref "U1") (pin "P103") (pinfunction "IO_L21N_2_P103") (pintype "bidirectional"))
    )
    (net (code "92") (name "unconnected-(U1D-IO_L21P_2-PadP102)") (class "Default")
      (node (ref "U1") (pin "P102") (pinfunction "IO_L21P_2_P102") (pintype "bidirectional"))
    )
    (net (code "93") (name "unconnected-(U1D-IO_L22N_2-PadP100)") (class "Default")
      (node (ref "U1") (pin "P100") (pinfunction "IO_L22N_2_P100") (pintype "bidirectional"))
    )
    (net (code "94") (name "unconnected-(U1D-IO_L22P_2-PadP99)") (class "Default")
      (node (ref "U1") (pin "P99") (pinfunction "IO_L22P_2_P99") (pintype "bidirectional"))
    )
    (net (code "95") (name "unconnected-(U1D-IO_L23N_2VREF_2-PadP98)") (class "Default")
      (node (ref "U1") (pin "P98") (pinfunction "IO_L23N_2VREF_2_P98") (pintype "bidirectional"))
    )
    (net (code "96") (name "unconnected-(U1D-IO_L23P_2-PadP97)") (class "Default")
      (node (ref "U1") (pin "P97") (pinfunction "IO_L23P_2_P97") (pintype "bidirectional"))
    )
    (net (code "97") (name "unconnected-(U1D-IO_L24N_2-PadP96)") (class "Default")
      (node (ref "U1") (pin "P96") (pinfunction "IO_L24N_2_P96") (pintype "bidirectional"))
    )
    (net (code "98") (name "unconnected-(U1D-IO_L24P_2-PadP95)") (class "Default")
      (node (ref "U1") (pin "P95") (pinfunction "IO_L24P_2_P95") (pintype "bidirectional"))
    )
    (net (code "99") (name "unconnected-(U1D-IO_L40N_2-PadP93)") (class "Default")
      (node (ref "U1") (pin "P93") (pinfunction "IO_L40N_2_P93") (pintype "bidirectional"))
    )
    (net (code "100") (name "unconnected-(U1D-IO_L40P_2VREF_2-PadP92)") (class "Default")
      (node (ref "U1") (pin "P92") (pinfunction "IO_L40P_2VREF_2_P92") (pintype "bidirectional"))
    )
    (net (code "101") (name "unconnected-(U1F-IO-PadP76)") (class "Default")
      (node (ref "U1") (pin "P76") (pinfunction "IO_P76") (pintype "bidirectional"))
    )
    (net (code "102") (name "unconnected-(U1F-IO_L01N_3VRP_3-PadP74)") (class "Default")
      (node (ref "U1") (pin "P74") (pinfunction "IO_L01N_3VRP_3_P74") (pintype "bidirectional"))
    )
    (net (code "103") (name "unconnected-(U1F-IO_L01P_3VRN_3-PadP73)") (class "Default")
      (node (ref "U1") (pin "P73") (pinfunction "IO_L01P_3VRN_3_P73") (pintype "bidirectional"))
    )
    (net (code "104") (name "unconnected-(U1F-IO_L20N_3-PadP78)") (class "Default")
      (node (ref "U1") (pin "P78") (pinfunction "IO_L20N_3_P78") (pintype "bidirectional"))
    )
    (net (code "105") (name "unconnected-(U1F-IO_L20P_3-PadP77)") (class "Default")
      (node (ref "U1") (pin "P77") (pinfunction "IO_L20P_3_P77") (pintype "bidirectional"))
    )
    (net (code "106") (name "unconnected-(U1F-IO_L21N_3-PadP80)") (class "Default")
      (node (ref "U1") (pin "P80") (pinfunction "IO_L21N_3_P80") (pintype "bidirectional"))
    )
    (net (code "107") (name "unconnected-(U1F-IO_L21P_3-PadP79)") (class "Default")
      (node (ref "U1") (pin "P79") (pinfunction "IO_L21P_3_P79") (pintype "bidirectional"))
    )
    (net (code "108") (name "unconnected-(U1F-IO_L22N_3-PadP83)") (class "Default")
      (node (ref "U1") (pin "P83") (pinfunction "IO_L22N_3_P83") (pintype "bidirectional"))
    )
    (net (code "109") (name "unconnected-(U1F-IO_L22P_3-PadP82)") (class "Default")
      (node (ref "U1") (pin "P82") (pinfunction "IO_L22P_3_P82") (pintype "bidirectional"))
    )
    (net (code "110") (name "unconnected-(U1F-IO_L23N_3-PadP85)") (class "Default")
      (node (ref "U1") (pin "P85") (pinfunction "IO_L23N_3_P85") (pintype "bidirectional"))
    )
    (net (code "111") (name "unconnected-(U1F-IO_L23P_3VREF_3-PadP84)") (class "Default")
      (node (ref "U1") (pin "P84") (pinfunction "IO_L23P_3VREF_3_P84") (pintype "bidirectional"))
    )
    (net (code "112") (name "unconnected-(U1F-IO_L24N_3-PadP87)") (class "Default")
      (node (ref "U1") (pin "P87") (pinfunction "IO_L24N_3_P87") (pintype "bidirectional"))
    )
    (net (code "113") (name "unconnected-(U1F-IO_L24P_3-PadP86)") (class "Default")
      (node (ref "U1") (pin "P86") (pinfunction "IO_L24P_3_P86") (pintype "bidirectional"))
    )
    (net (code "114") (name "unconnected-(U1F-IO_L40N_3VREF_3-PadP90)") (class "Default")
      (node (ref "U1") (pin "P90") (pinfunction "IO_L40N_3VREF_3_P90") (pintype "bidirectional"))
    )
    (net (code "115") (name "unconnected-(U1F-IO_L40P_3-PadP89)") (class "Default")
      (node (ref "U1") (pin "P89") (pinfunction "IO_L40P_3_P89") (pintype "bidirectional"))
    )
    (net (code "116") (name "unconnected-(U1G-IOVREF_4-PadP70)") (class "Default")
      (node (ref "U1") (pin "P70") (pinfunction "IOVREF_4_P70") (pintype "bidirectional"))
    )
    (net (code "117") (name "unconnected-(U1G-IO_L01N_4VRP_4-PadP69)") (class "Default")
      (node (ref "U1") (pin "P69") (pinfunction "IO_L01N_4VRP_4_P69") (pintype "bidirectional"))
    )
    (net (code "118") (name "unconnected-(U1G-IO_L01P_4VRN_4-PadP68)") (class "Default")
      (node (ref "U1") (pin "P68") (pinfunction "IO_L01P_4VRN_4_P68") (pintype "bidirectional"))
    )
    (net (code "119") (name "unconnected-(U1G-IO_L27P_4D1-PadP63)") (class "Default")
      (node (ref "U1") (pin "P63") (pinfunction "IO_L27P_4D1_P63") (pintype "bidirectional"))
    )
    (net (code "120") (name "unconnected-(U1G-IO_L30N_4D2-PadP60)") (class "Default")
      (node (ref "U1") (pin "P60") (pinfunction "IO_L30N_4D2_P60") (pintype "bidirectional"))
    )
    (net (code "121") (name "unconnected-(U1G-IO_L30P_4D3-PadP59)") (class "Default")
      (node (ref "U1") (pin "P59") (pinfunction "IO_L30P_4D3_P59") (pintype "bidirectional"))
    )
    (net (code "122") (name "unconnected-(U1G-IO_L31P_4DOUTBUSY-PadP57)") (class "Default")
      (node (ref "U1") (pin "P57") (pinfunction "IO_L31P_4DOUTBUSY_P57") (pintype "bidirectional"))
    )
    (net (code "123") (name "unconnected-(U1G-IO_L32N_4GCLK1-PadP56)") (class "Default")
      (node (ref "U1") (pin "P56") (pinfunction "IO_L32N_4GCLK1_P56") (pintype "bidirectional"))
    )
    (net (code "124") (name "unconnected-(U1G-IO_L32P_4GCLK0-PadP55)") (class "Default")
      (node (ref "U1") (pin "P55") (pinfunction "IO_L32P_4GCLK0_P55") (pintype "bidirectional"))
    )
    (net (code "125") (name "unconnected-(U1I-IOVREF_5-PadP44)") (class "Default")
      (node (ref "U1") (pin "P44") (pinfunction "IOVREF_5_P44") (pintype "bidirectional"))
    )
    (net (code "126") (name "unconnected-(U1I-IO_L01N_5RDWR_B-PadP41)") (class "Default")
      (node (ref "U1") (pin "P41") (pinfunction "IO_L01N_5RDWR_B_P41") (pintype "bidirectional"))
    )
    (net (code "127") (name "unconnected-(U1I-IO_L01P_5CS_B-PadP40)") (class "Default")
      (node (ref "U1") (pin "P40") (pinfunction "IO_L01P_5CS_B_P40") (pintype "bidirectional"))
    )
    (net (code "128") (name "unconnected-(U1I-IO_L28N_5D6-PadP47)") (class "Default")
      (node (ref "U1") (pin "P47") (pinfunction "IO_L28N_5D6_P47") (pintype "bidirectional"))
    )
    (net (code "129") (name "unconnected-(U1I-IO_L28P_5D7-PadP46)") (class "Default")
      (node (ref "U1") (pin "P46") (pinfunction "IO_L28P_5D7_P46") (pintype "bidirectional"))
    )
    (net (code "130") (name "unconnected-(U1I-IO_L31N_5D4-PadP51)") (class "Default")
      (node (ref "U1") (pin "P51") (pinfunction "IO_L31N_5D4_P51") (pintype "bidirectional"))
    )
    (net (code "131") (name "unconnected-(U1I-IO_L31P_5D5-PadP50)") (class "Default")
      (node (ref "U1") (pin "P50") (pinfunction "IO_L31P_5D5_P50") (pintype "bidirectional"))
    )
    (net (code "132") (name "unconnected-(U1I-IO_L32N_5GCLK3-PadP53)") (class "Default")
      (node (ref "U1") (pin "P53") (pinfunction "IO_L32N_5GCLK3_P53") (pintype "bidirectional"))
    )
    (net (code "133") (name "unconnected-(U1I-IO_L32P_5GCLK2-PadP52)") (class "Default")
      (node (ref "U1") (pin "P52") (pinfunction "IO_L32P_5GCLK2_P52") (pintype "bidirectional"))
    )
    (net (code "134") (name "unconnected-(U1N-HSWAP_EN-PadP142)") (class "Default")
      (node (ref "U1") (pin "P142") (pinfunction "HSWAP_EN_P142") (pintype "bidirectional"))
    )
  )
)
